# MCU.net
KiCad netlist of a schematic drawn in Altium Designer
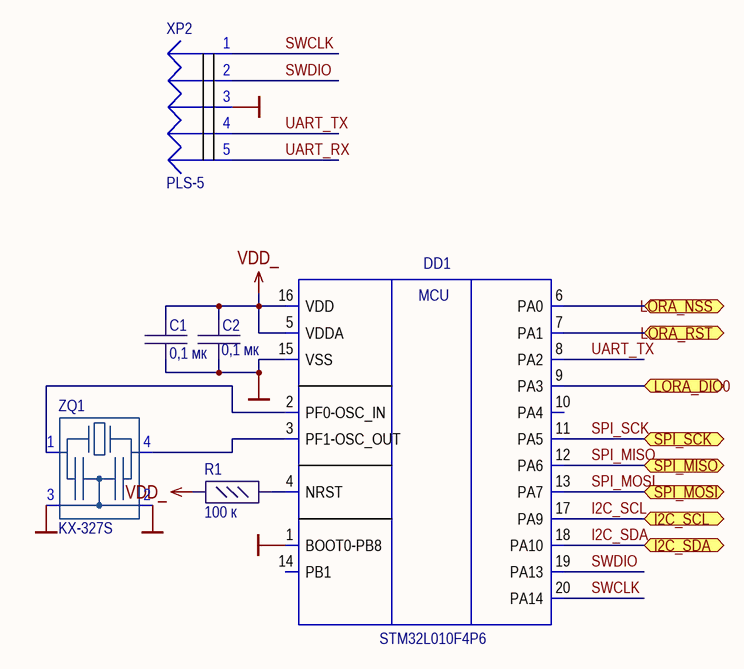
[diagram p0: MCU.SchDoc]

(export (version "E")
  (design (tool "Eeschema 10.0.6"))
  (components
    (comp (ref "C1")
      (value "0,1 мк")
      (footprint "C_0603")
      (description "CAP CER 0.1UF 100V X7R 0603")
      (fields
        (field (name "PART NUMBER") "GRM188R72A104MA35D")
        (field (name "MANUFACTURER") "Murata Electronics")
      )
      (libsource (lib "Database_Lib") (part "Capasitor"))
    )
    (comp (ref "C2")
      (value "0,1 мк")
      (footprint "C_0603")
      (description "CAP CER 0.1UF 100V X7R 0603")
      (fields
        (field (name "PART NUMBER") "GRM188R72A104MA35D")
        (field (name "MANUFACTURER") "Murata Electronics")
      )
      (libsource (lib "Database_Lib") (part "Capasitor"))
    )
    (comp (ref "DD1")
      (value "STM32L010F4P6")
      (footprint "TSSOP-20")
      (libsource (lib "6.Chips") (part "STM32L010F4P6"))
    )
    (comp (ref "R1")
      (value "100 к")
      (footprint "R_0603")
      (description "RES SMD 10K OHM 1% 1/10W 0603")
      (fields (field (name "PART NUMBER") "CR0603-FX-1002ELF") (field (name "MANUFACTURER") "Bourns Inc."))
      (libsource (lib "Database_Lib") (part "Resistor"))
    )
    (comp (ref "XP2") (value "PLS-5") (footprint "PLS-5") (libsource (lib "7.Connectors") (part "PLS-5")))
    (comp (ref "ZQ1")
      (value "KX-327S")
      (footprint "KX-327S")
      (description "Кварцевый резонатор 32.768 кГц, 20 ppm")
      (libsource (lib "8.Resonarors") (part "KX-327S"))
    )
  )
  (nets
    (net (code "1") (name "/I2C_SCL") (class "Default")
      (node (ref "DD1") (pin "17") (pinfunction "PA9_17") (pintype "passive"))
    )
    (net (code "2") (name "/I2C_SDA") (class "Default")
      (node (ref "DD1") (pin "18") (pinfunction "PA10_18") (pintype "passive"))
    )
    (net (code "3") (name "/LORA_DIO0") (class "Default")
      (node (ref "DD1") (pin "9") (pinfunction "PA3_9") (pintype "passive"))
    )
    (net (code "4") (name "/LORA_NSS") (class "Default")
      (node (ref "DD1") (pin "6") (pinfunction "PA0_6") (pintype "passive"))
    )
    (net (code "5") (name "/LORA_RST") (class "Default")
      (node (ref "DD1") (pin "7") (pinfunction "PA1_7") (pintype "passive"))
    )
    (net (code "6") (name "/SPI_MISO") (class "Default")
      (node (ref "DD1") (pin "12") (pinfunction "PA6_12") (pintype "passive"))
    )
    (net (code "7") (name "/SPI_MOSI") (class "Default")
      (node (ref "DD1") (pin "13") (pinfunction "PA7_13") (pintype "passive"))
    )
    (net (code "8") (name "/SPI_SCK") (class "Default")
      (node (ref "DD1") (pin "11") (pinfunction "PA5_11") (pintype "passive"))
    )
    (net (code "9") (name "/SWCLK") (class "Default")
      (node (ref "DD1") (pin "20") (pinfunction "PA14_20") (pintype "passive"))
      (node (ref "XP2") (pin "1") (pinfunction "1_1") (pintype "passive"))
    )
    (net (code "10") (name "/SWDIO") (class "Default")
      (node (ref "DD1") (pin "19") (pinfunction "PA13_19") (pintype "passive"))
      (node (ref "XP2") (pin "2") (pinfunction "2_2") (pintype "passive"))
    )
    (net (code "11") (name "/UART_RX") (class "Default")
      (node (ref "XP2") (pin "5") (pinfunction "5_5") (pintype "passive"))
    )
    (net (code "12") (name "/UART_TX") (class "Default")
      (node (ref "DD1") (pin "8") (pinfunction "PA2_8") (pintype "passive"))
      (node (ref "XP2") (pin "4") (pinfunction "4_4") (pintype "passive"))
    )
    (net (code "13") (name "GND") (class "Default")
      (node (ref "C1") (pin "1") (pinfunction "1_1") (pintype "passive"))
      (node (ref "C2") (pin "1") (pinfunction "1_1") (pintype "passive"))
      (node (ref "DD1") (pin "1") (pinfunction "BOOT0-PB8_1") (pintype "passive"))
      (node (ref "DD1") (pin "15") (pinfunction "VSS_15") (pintype "passive"))
      (node (ref "XP2") (pin "3") (pinfunction "3_3") (pintype "passive"))
      (node (ref "ZQ1") (pin "2") (pinfunction "2_2") (pintype "passive"))
      (node (ref "ZQ1") (pin "3") (pinfunction "3_3") (pintype "passive"))
    )
    (net (code "14") (name "Net-(DD1-NRST)") (class "Default")
      (node (ref "DD1") (pin "4") (pinfunction "NRST_4") (pintype "passive"))
      (node (ref "R1") (pin "2") (pinfunction "2_2") (pintype "passive"))
    )
    (net (code "15") (name "Net-(DD1-PF0-OSC_IN)") (class "Default")
      (node (ref "DD1") (pin "2") (pinfunction "PF0-OSC_IN_2") (pintype "passive"))
      (node (ref "ZQ1") (pin "1") (pinfunction "1_1") (pintype "passive"))
    )
    (net (code "16") (name "Net-(DD1-PF1-OSC_OUT)") (class "Default")
      (node (ref "DD1") (pin "3") (pinfunction "PF1-OSC_OUT_3") (pintype "passive"))
      (node (ref "ZQ1") (pin "4") (pinfunction "4_4") (pintype "passive"))
    )
    (net (code "17") (name "VDD_") (class "Default")
      (node (ref "C1") (pin "2") (pinfunction "2_2") (pintype "passive"))
      (node (ref "C2") (pin "2") (pinfunction "2_2") (pintype "passive"))
      (node (ref "DD1") (pin "16") (pinfunction "VDD_16") (pintype "passive"))
      (node (ref "DD1") (pin "5") (pinfunction "VDDA_5") (pintype "passive"))
      (node (ref "R1") (pin "1") (pinfunction "1_1") (pintype "passive"))
    )
    (net (code "18") (name "unconnected-(DD1-PA4-Pad10)") (class "Default")
      (node (ref "DD1") (pin "10") (pinfunction "PA4_10") (pintype "passive"))
    )
    (net (code "19") (name "unconnected-(DD1-PB1-Pad14)") (class "Default")
      (node (ref "DD1") (pin "14") (pinfunction "PB1_14") (pintype "passive"))
    )
  )
)
